# ADCSHubV2.net
KiCad netlist of a schematic drawn in Altium Designer
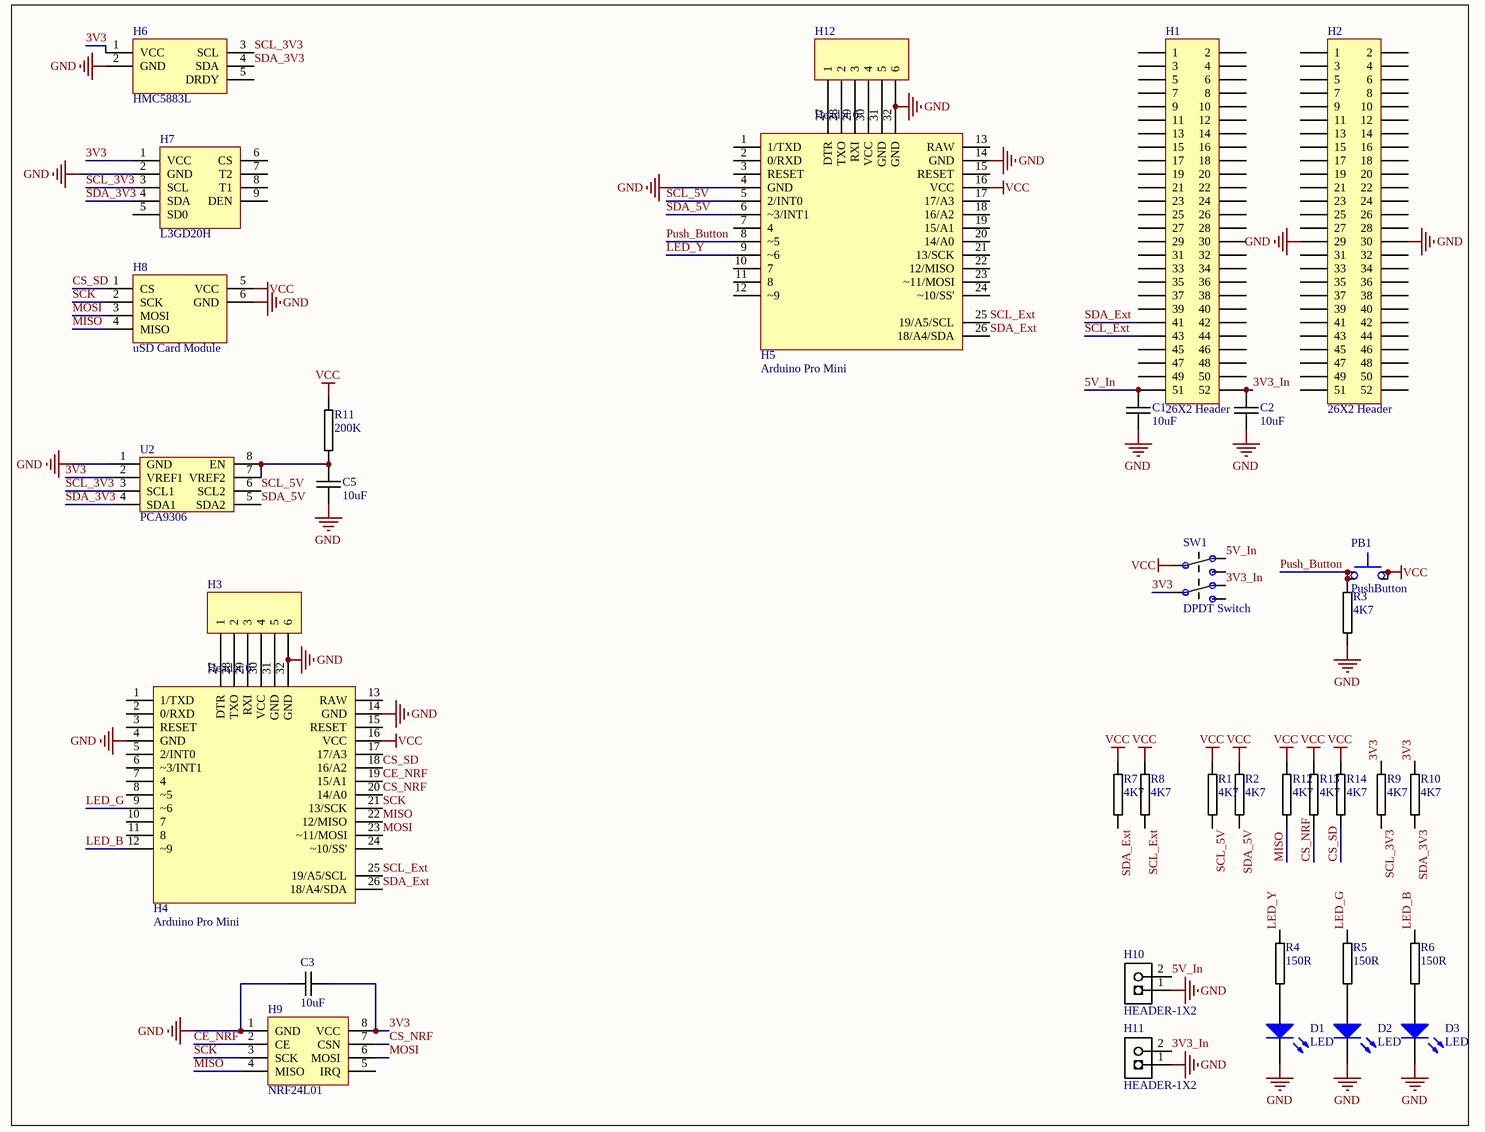
[diagram p0: ADCSHubV2.SchDoc]

(export (version "E")
  (design (tool "Eeschema 10.0.6"))
  (components
    (comp (ref "C1")
      (value "10uF")
      (footprint "0805C-TBD")
      (description "CAPACITOR 0805 CERAMIC")
      (libsource (lib "vh_altium_library") (part "0805C-100nF-25V-X7R-MUR"))
    )
    (comp (ref "C2")
      (value "10uF")
      (footprint "0805C-TBD")
      (description "CAPACITOR 0805 CERAMIC")
      (libsource (lib "vh_altium_library") (part "0805C-100nF-25V-X7R-MUR"))
    )
    (comp (ref "C3")
      (value "10uF")
      (footprint "0805C-GENERIC")
      (description "CAPACITOR 0805 CERAMIC")
      (fields
        (field (name "MANUFACTURER PART NUMBER") "C2012X5R1C106M")
        (field (name "MANUFACTURER") "TDK Corporation")
      )
      (libsource (lib "vh_altium_library") (part "0805C-10UF-16V-X5R-TDK"))
    )
    (comp (ref "C5")
      (value "10uF")
      (footprint "0805C-GENERIC")
      (description "CAPACITOR 0805 CERAMIC")
      (fields
        (field (name "MANUFACTURER PART NUMBER") "C2012X5R1C106M")
        (field (name "MANUFACTURER") "TDK Corporation")
      )
      (libsource (lib "vh_altium_library") (part "0805C-10UF-16V-X5R-TDK"))
    )
    (comp (ref "D1")
      (value "LED")
      (footprint "LED")
      (description "Small LED")
      (libsource (lib "SupportComponents") (part "LED"))
    )
    (comp (ref "D2")
      (value "LED")
      (footprint "LED")
      (description "Small LED")
      (libsource (lib "SupportComponents") (part "LED"))
    )
    (comp (ref "D3")
      (value "LED")
      (footprint "LED")
      (description "Small LED")
      (libsource (lib "SupportComponents") (part "LED"))
    )
    (comp (ref "H1")
      (value "26X2 Header")
      (footprint "26X2 Header")
      (libsource (lib "SupportComponents") (part "26X2 Header"))
    )
    (comp (ref "H2")
      (value "26X2 Header")
      (footprint "26X2 Header")
      (libsource (lib "SupportComponents") (part "26X2 Header"))
    )
    (comp (ref "H3")
      (value "Header 6")
      (footprint "HDR1X6")
      (description "Header, 6-Pin")
      (fields (field (name "PUBLISHER") "Altium Limited"))
      (libsource (lib "Miscellaneous Connectors") (part "Header 6"))
    )
    (comp (ref "H4")
      (value "Arduino Pro Mini")
      (footprint "Arduino Pro Mini")
      (libsource (lib "SupportComponents") (part "Arduino Pro Mini"))
    )
    (comp (ref "H5")
      (value "Arduino Pro Mini")
      (footprint "Arduino Pro Mini")
      (libsource (lib "SupportComponents") (part "Arduino Pro Mini"))
    )
    (comp (ref "H6")
      (value "HMC5883L")
      (footprint "HMC5883L")
      (description "Magnetometer")
      (libsource (lib "SupportComponents") (part "HMC5883L"))
    )
    (comp (ref "H7")
      (value "L3GD20H")
      (footprint "L3GD20H")
      (description "Gyroscope")
      (libsource (lib "SupportComponents") (part "L3GD20H"))
    )
    (comp (ref "H8")
      (value "uSD Card Module")
      (footprint "uSD Card Module")
      (libsource (lib "SupportComponents") (part "uSD Card Module"))
    )
    (comp (ref "H9")
      (value "NRF24L01")
      (footprint "NRF24L01")
      (description "Radio Transceiver")
      (libsource (lib "SupportComponents") (part "NRF24L01"))
    )
    (comp (ref "H10")
      (value "HEADER-1X2")
      (footprint "HEADER-1X2")
      (libsource (lib "vh_altium_library") (part "HEADER-1X2"))
    )
    (comp (ref "H11")
      (value "HEADER-1X2")
      (footprint "HEADER-1X2")
      (libsource (lib "vh_altium_library") (part "HEADER-1X2"))
    )
    (comp (ref "H12")
      (value "Header 6")
      (footprint "HDR1X6")
      (description "Header, 6-Pin")
      (fields (field (name "PUBLISHER") "Altium Limited"))
      (libsource (lib "Miscellaneous Connectors") (part "Header 6"))
    )
    (comp (ref "PB1")
      (value "PushButton")
      (footprint "PushButton")
      (libsource (lib "SupportComponents") (part "PushButton"))
    )
    (comp (ref "R1")
      (value "4K7")
      (footprint "0805R-4K7")
      (description "RESISTOR 0805 1/4 WATT THIN FILM")
      (libsource (lib "vh_altium_library") (part "0805R-4K7"))
    )
    (comp (ref "R2")
      (value "4K7")
      (footprint "0805R-4K7")
      (description "RESISTOR 0805 1/4 WATT THIN FILM")
      (libsource (lib "vh_altium_library") (part "0805R-4K7"))
    )
    (comp (ref "R3")
      (value "4K7")
      (footprint "0805R-4K7")
      (description "RESISTOR 0805 1/4 WATT THIN FILM")
      (libsource (lib "vh_altium_library") (part "0805R-4K7"))
    )
    (comp (ref "R4")
      (value "150R")
      (footprint "0805R-150")
      (description "RESISTOR 0805 1/4 WATT THIN FILM")
      (libsource (lib "vh_altium_library") (part "0805R-150"))
    )
    (comp (ref "R5")
      (value "150R")
      (footprint "0805R-150")
      (description "RESISTOR 0805 1/4 WATT THIN FILM")
      (libsource (lib "vh_altium_library") (part "0805R-150"))
    )
    (comp (ref "R6")
      (value "150R")
      (footprint "0805R-150")
      (description "RESISTOR 0805 1/4 WATT THIN FILM")
      (libsource (lib "vh_altium_library") (part "0805R-150"))
    )
    (comp (ref "R7")
      (value "4K7")
      (footprint "0805R-4K7")
      (description "RESISTOR 0805 1/4 WATT THIN FILM")
      (libsource (lib "vh_altium_library") (part "0805R-4K7"))
    )
    (comp (ref "R8")
      (value "4K7")
      (footprint "0805R-4K7")
      (description "RESISTOR 0805 1/4 WATT THIN FILM")
      (libsource (lib "vh_altium_library") (part "0805R-4K7"))
    )
    (comp (ref "R9")
      (value "4K7")
      (footprint "0805R-4K7")
      (description "RESISTOR 0805 1/4 WATT THIN FILM")
      (libsource (lib "vh_altium_library") (part "0805R-4K7"))
    )
    (comp (ref "R10")
      (value "4K7")
      (footprint "0805R-4K7")
      (description "RESISTOR 0805 1/4 WATT THIN FILM")
      (libsource (lib "vh_altium_library") (part "0805R-4K7"))
    )
    (comp (ref "R11")
      (value "200K")
      (footprint "0805R-4K7")
      (description "RESISTOR 0805 1/4 WATT THIN FILM")
      (libsource (lib "vh_altium_library") (part "0805R-4K7"))
    )
    (comp (ref "R12")
      (value "4K7")
      (footprint "0805R-4K7")
      (description "RESISTOR 0805 1/4 WATT THIN FILM")
      (libsource (lib "vh_altium_library") (part "0805R-4K7"))
    )
    (comp (ref "R13")
      (value "4K7")
      (footprint "0805R-4K7")
      (description "RESISTOR 0805 1/4 WATT THIN FILM")
      (libsource (lib "vh_altium_library") (part "0805R-4K7"))
    )
    (comp (ref "R14")
      (value "4K7")
      (footprint "0805R-4K7")
      (description "RESISTOR 0805 1/4 WATT THIN FILM")
      (libsource (lib "vh_altium_library") (part "0805R-4K7"))
    )
    (comp (ref "SW1")
      (value "DPDT Switch")
      (footprint "DPDT SWITCH")
      (libsource (lib "SupportComponents") (part "DPDT Switch"))
    )
    (comp (ref "U2")
      (value "PCA9306")
      (footprint "PCA9306 (DCT)")
      (description "Dual Bidirectional I2C Voltage Level Translator")
      (libsource (lib "SupportComponents") (part "PCA9306"))
    )
  )
  (nets
    (net (code "1") (name "/3V3") (class "Default")
      (node (ref "C3") (pin "2") (pintype "passive"))
      (node (ref "H6") (pin "1") (pinfunction "VCC_1") (pintype "passive"))
      (node (ref "H7") (pin "1") (pinfunction "VCC_1") (pintype "passive"))
      (node (ref "H9") (pin "8") (pinfunction "VCC_8") (pintype "passive"))
      (node (ref "R10") (pin "1") (pintype "passive"))
      (node (ref "R9") (pin "1") (pintype "passive"))
      (node (ref "SW1") (pin "5") (pinfunction "5_5") (pintype "passive"))
      (node (ref "U2") (pin "2") (pinfunction "VREF1_2") (pintype "passive"))
    )
    (net (code "2") (name "/3V3_In") (class "Default")
      (node (ref "C2") (pin "1") (pintype "passive"))
      (node (ref "H1") (pin "52") (pinfunction "52_52") (pintype "passive"))
      (node (ref "H11") (pin "2") (pintype "passive"))
      (node (ref "SW1") (pin "4") (pinfunction "4_4") (pintype "passive"))
    )
    (net (code "3") (name "/5V_In") (class "Default")
      (node (ref "C1") (pin "1") (pintype "passive"))
      (node (ref "H1") (pin "51") (pinfunction "51_51") (pintype "passive"))
      (node (ref "H10") (pin "2") (pintype "passive"))
      (node (ref "SW1") (pin "1") (pinfunction "1_1") (pintype "passive"))
    )
    (net (code "4") (name "/CE_NRF") (class "Default")
      (node (ref "H4") (pin "19") (pinfunction "15/A1_19") (pintype "passive"))
      (node (ref "H9") (pin "2") (pinfunction "CE_2") (pintype "passive"))
    )
    (net (code "5") (name "/CS_NRF") (class "Default")
      (node (ref "H4") (pin "20") (pinfunction "14/A0_20") (pintype "passive"))
      (node (ref "H9") (pin "7") (pinfunction "CSN_7") (pintype "passive"))
      (node (ref "R13") (pin "2") (pintype "passive"))
    )
    (net (code "6") (name "/CS_SD") (class "Default")
      (node (ref "H4") (pin "18") (pinfunction "16/A2_18") (pintype "passive"))
      (node (ref "H8") (pin "1") (pinfunction "CS_1") (pintype "passive"))
      (node (ref "R14") (pin "2") (pintype "passive"))
    )
    (net (code "7") (name "/LED_B") (class "Default")
      (node (ref "H4") (pin "12") (pinfunction "~9_12") (pintype "passive"))
      (node (ref "R6") (pin "1") (pintype "passive"))
    )
    (net (code "8") (name "/LED_G") (class "Default")
      (node (ref "H4") (pin "9") (pinfunction "~6_9") (pintype "passive"))
      (node (ref "R5") (pin "1") (pintype "passive"))
    )
    (net (code "9") (name "/LED_Y") (class "Default")
      (node (ref "H5") (pin "9") (pinfunction "~6_9") (pintype "passive"))
      (node (ref "R4") (pin "1") (pintype "passive"))
    )
    (net (code "10") (name "/MISO") (class "Default")
      (node (ref "H4") (pin "22") (pinfunction "12/MISO_22") (pintype "passive"))
      (node (ref "H8") (pin "4") (pinfunction "MISO_4") (pintype "passive"))
      (node (ref "H9") (pin "4") (pinfunction "MISO_4") (pintype "passive"))
      (node (ref "R12") (pin "2") (pintype "passive"))
    )
    (net (code "11") (name "/MOSI") (class "Default")
      (node (ref "H4") (pin "23") (pinfunction "~11/MOSI_23") (pintype "passive"))
      (node (ref "H8") (pin "3") (pinfunction "MOSI_3") (pintype "passive"))
      (node (ref "H9") (pin "6") (pinfunction "MOSI_6") (pintype "passive"))
    )
    (net (code "12") (name "/Push_Button") (class "Default")
      (node (ref "H5") (pin "8") (pinfunction "~5_8") (pintype "passive"))
      (node (ref "PB1") (pin "26") (pinfunction "26_26") (pintype "passive"))
      (node (ref "PB1") (pin "28") (pinfunction "28_28") (pintype "passive"))
      (node (ref "R3") (pin "1") (pintype "passive"))
    )
    (net (code "13") (name "/SCK") (class "Default")
      (node (ref "H4") (pin "21") (pinfunction "13/SCK_21") (pintype "passive"))
      (node (ref "H8") (pin "2") (pinfunction "SCK_2") (pintype "passive"))
      (node (ref "H9") (pin "3") (pinfunction "SCK_3") (pintype "passive"))
    )
    (net (code "14") (name "/SCL_3V3") (class "Default")
      (node (ref "H6") (pin "3") (pinfunction "SCL_3") (pintype "passive"))
      (node (ref "H7") (pin "3") (pinfunction "SCL_3") (pintype "passive"))
      (node (ref "R9") (pin "2") (pintype "passive"))
      (node (ref "U2") (pin "3") (pinfunction "SCL1_3") (pintype "passive"))
    )
    (net (code "15") (name "/SCL_5V") (class "Default")
      (node (ref "H5") (pin "5") (pinfunction "2/INT0_5") (pintype "passive"))
      (node (ref "R1") (pin "2") (pintype "passive"))
      (node (ref "U2") (pin "6") (pinfunction "SCL2_6") (pintype "passive"))
    )
    (net (code "16") (name "/SCL_Ext") (class "Default")
      (node (ref "H1") (pin "43") (pinfunction "43_43") (pintype "passive"))
      (node (ref "H4") (pin "25") (pinfunction "19/A5/SCL_25") (pintype "passive"))
      (node (ref "H5") (pin "25") (pinfunction "19/A5/SCL_25") (pintype "passive"))
      (node (ref "R8") (pin "2") (pintype "passive"))
    )
    (net (code "17") (name "/SDA_3V3") (class "Default")
      (node (ref "H6") (pin "4") (pinfunction "SDA_4") (pintype "passive"))
      (node (ref "H7") (pin "4") (pinfunction "SDA_4") (pintype "passive"))
      (node (ref "R10") (pin "2") (pintype "passive"))
      (node (ref "U2") (pin "4") (pinfunction "SDA1_4") (pintype "passive"))
    )
    (net (code "18") (name "/SDA_5V") (class "Default")
      (node (ref "H5") (pin "6") (pinfunction "~3/INT1_6") (pintype "passive"))
      (node (ref "R2") (pin "2") (pintype "passive"))
      (node (ref "U2") (pin "5") (pinfunction "SDA2_5") (pintype "passive"))
    )
    (net (code "19") (name "/SDA_Ext") (class "Default")
      (node (ref "H1") (pin "41") (pinfunction "41_41") (pintype "passive"))
      (node (ref "H4") (pin "26") (pinfunction "18/A4/SDA_26") (pintype "passive"))
      (node (ref "H5") (pin "26") (pinfunction "18/A4/SDA_26") (pintype "passive"))
      (node (ref "R7") (pin "2") (pintype "passive"))
    )
    (net (code "20") (name "GND") (class "Default")
      (node (ref "C1") (pin "2") (pintype "passive"))
      (node (ref "C2") (pin "2") (pintype "passive"))
      (node (ref "C3") (pin "1") (pintype "passive"))
      (node (ref "C5") (pin "2") (pintype "passive"))
      (node (ref "D1") (pin "2") (pinfunction "K_2") (pintype "passive"))
      (node (ref "D2") (pin "2") (pinfunction "K_2") (pintype "passive"))
      (node (ref "D3") (pin "2") (pinfunction "K_2") (pintype "passive"))
      (node (ref "H10") (pin "1") (pintype "passive"))
      (node (ref "H11") (pin "1") (pintype "passive"))
      (node (ref "H12") (pin "6") (pinfunction "6_6") (pintype "passive"))
      (node (ref "H2") (pin "29") (pinfunction "29_29") (pintype "passive"))
      (node (ref "H2") (pin "30") (pinfunction "30_30") (pintype "passive"))
      (node (ref "H3") (pin "6") (pinfunction "6_6") (pintype "passive"))
      (node (ref "H4") (pin "14") (pinfunction "GND_14") (pintype "passive"))
      (node (ref "H4") (pin "32") (pinfunction "GND_32") (pintype "passive"))
      (node (ref "H4") (pin "4") (pinfunction "GND_4") (pintype "passive"))
      (node (ref "H5") (pin "14") (pinfunction "GND_14") (pintype "passive"))
      (node (ref "H5") (pin "32") (pinfunction "GND_32") (pintype "passive"))
      (node (ref "H5") (pin "4") (pinfunction "GND_4") (pintype "passive"))
      (node (ref "H6") (pin "2") (pinfunction "GND_2") (pintype "passive"))
      (node (ref "H7") (pin "2") (pinfunction "GND_2") (pintype "passive"))
      (node (ref "H8") (pin "6") (pinfunction "GND_6") (pintype "passive"))
      (node (ref "H9") (pin "1") (pinfunction "GND_1") (pintype "passive"))
      (node (ref "R3") (pin "2") (pintype "passive"))
      (node (ref "U2") (pin "1") (pinfunction "GND_1") (pintype "passive"))
    )
    (net (code "21") (name "Net-(D1-A)") (class "Default")
      (node (ref "D1") (pin "1") (pinfunction "A_1") (pintype "passive"))
      (node (ref "R4") (pin "2") (pintype "passive"))
    )
    (net (code "22") (name "Net-(D2-A)") (class "Default")
      (node (ref "D2") (pin "1") (pinfunction "A_1") (pintype "passive"))
      (node (ref "R5") (pin "2") (pintype "passive"))
    )
    (net (code "23") (name "Net-(D3-A)") (class "Default")
      (node (ref "D3") (pin "1") (pinfunction "A_1") (pintype "passive"))
      (node (ref "R6") (pin "2") (pintype "passive"))
    )
    (net (code "24") (name "Net-(H3-Pad4)") (class "Default")
      (node (ref "H3") (pin "4") (pinfunction "4_4") (pintype "passive"))
      (node (ref "H4") (pin "30") (pinfunction "VCC_30") (pintype "passive"))
    )
    (net (code "25") (name "Net-(H3-Pad5)") (class "Default")
      (node (ref "H3") (pin "5") (pinfunction "5_5") (pintype "passive"))
      (node (ref "H4") (pin "31") (pinfunction "GND_31") (pintype "passive"))
    )
    (net (code "26") (name "Net-(H4-DTR)") (class "Default")
      (node (ref "H3") (pin "1") (pinfunction "1_1") (pintype "passive"))
      (node (ref "H4") (pin "27") (pinfunction "DTR_27") (pintype "passive"))
    )
    (net (code "27") (name "Net-(H4-RXI)") (class "Default")
      (node (ref "H3") (pin "3") (pinfunction "3_3") (pintype "passive"))
      (node (ref "H4") (pin "29") (pinfunction "RXI_29") (pintype "passive"))
    )
    (net (code "28") (name "Net-(H4-TXO)") (class "Default")
      (node (ref "H3") (pin "2") (pinfunction "2_2") (pintype "passive"))
      (node (ref "H4") (pin "28") (pinfunction "TXO_28") (pintype "passive"))
    )
    (net (code "29") (name "Net-(H5-DTR)") (class "Default")
      (node (ref "H12") (pin "1") (pinfunction "1_1") (pintype "passive"))
      (node (ref "H5") (pin "27") (pinfunction "DTR_27") (pintype "passive"))
    )
    (net (code "30") (name "Net-(H5-RXI)") (class "Default")
      (node (ref "H12") (pin "3") (pinfunction "3_3") (pintype "passive"))
      (node (ref "H5") (pin "29") (pinfunction "RXI_29") (pintype "passive"))
    )
    (net (code "31") (name "Net-(H5-TXO)") (class "Default")
      (node (ref "H12") (pin "2") (pinfunction "2_2") (pintype "passive"))
      (node (ref "H5") (pin "28") (pinfunction "TXO_28") (pintype "passive"))
    )
    (net (code "32") (name "Net-(H12-Pad4)") (class "Default")
      (node (ref "H12") (pin "4") (pinfunction "4_4") (pintype "passive"))
      (node (ref "H5") (pin "30") (pinfunction "VCC_30") (pintype "passive"))
    )
    (net (code "33") (name "Net-(H12-Pad5)") (class "Default")
      (node (ref "H12") (pin "5") (pinfunction "5_5") (pintype "passive"))
      (node (ref "H5") (pin "31") (pinfunction "GND_31") (pintype "passive"))
    )
    (net (code "34") (name "Net-(U2-EN)") (class "Default")
      (node (ref "C5") (pin "1") (pintype "passive"))
      (node (ref "R11") (pin "1") (pintype "passive"))
      (node (ref "U2") (pin "7") (pinfunction "VREF2_7") (pintype "passive"))
      (node (ref "U2") (pin "8") (pinfunction "EN_8") (pintype "passive"))
    )
    (net (code "35") (name "VCC") (class "Default")
      (node (ref "H4") (pin "16") (pinfunction "VCC_16") (pintype "passive"))
      (node (ref "H5") (pin "16") (pinfunction "VCC_16") (pintype "passive"))
      (node (ref "H8") (pin "5") (pinfunction "VCC_5") (pintype "passive"))
      (node (ref "PB1") (pin "27") (pinfunction "27_27") (pintype "passive"))
      (node (ref "PB1") (pin "29") (pinfunction "29_29") (pintype "passive"))
      (node (ref "R1") (pin "1") (pintype "passive"))
      (node (ref "R11") (pin "2") (pintype "passive"))
      (node (ref "R12") (pin "1") (pintype "passive"))
      (node (ref "R13") (pin "1") (pintype "passive"))
      (node (ref "R14") (pin "1") (pintype "passive"))
      (node (ref "R2") (pin "1") (pintype "passive"))
      (node (ref "R7") (pin "1") (pintype "passive"))
      (node (ref "R8") (pin "1") (pintype "passive"))
      (node (ref "SW1") (pin "2") (pinfunction "2_2") (pintype "passive"))
    )
    (net (code "36") (name "unconnected-(H1-Pad1)") (class "Default")
      (node (ref "H1") (pin "1") (pinfunction "1_1") (pintype "passive"))
    )
    (net (code "37") (name "unconnected-(H1-Pad2)") (class "Default")
      (node (ref "H1") (pin "2") (pinfunction "2_2") (pintype "passive"))
    )
    (net (code "38") (name "unconnected-(H1-Pad3)") (class "Default")
      (node (ref "H1") (pin "3") (pinfunction "3_3") (pintype "passive"))
    )
    (net (code "39") (name "unconnected-(H1-Pad4)") (class "Default")
      (node (ref "H1") (pin "4") (pinfunction "4_4") (pintype "passive"))
    )
    (net (code "40") (name "unconnected-(H1-Pad5)") (class "Default")
      (node (ref "H1") (pin "5") (pinfunction "5_5") (pintype "passive"))
    )
    (net (code "41") (name "unconnected-(H1-Pad6)") (class "Default")
      (node (ref "H1") (pin "6") (pinfunction "6_6") (pintype "passive"))
    )
    (net (code "42") (name "unconnected-(H1-Pad7)") (class "Default")
      (node (ref "H1") (pin "7") (pinfunction "7_7") (pintype "passive"))
    )
    (net (code "43") (name "unconnected-(H1-Pad8)") (class "Default")
      (node (ref "H1") (pin "8") (pinfunction "8_8") (pintype "passive"))
    )
    (net (code "44") (name "unconnected-(H1-Pad9)") (class "Default")
      (node (ref "H1") (pin "9") (pinfunction "9_9") (pintype "passive"))
    )
    (net (code "45") (name "unconnected-(H1-Pad10)") (class "Default")
      (node (ref "H1") (pin "10") (pinfunction "10_10") (pintype "passive"))
    )
    (net (code "46") (name "unconnected-(H1-Pad11)") (class "Default")
      (node (ref "H1") (pin "11") (pinfunction "11_11") (pintype "passive"))
    )
    (net (code "47") (name "unconnected-(H1-Pad12)") (class "Default")
      (node (ref "H1") (pin "12") (pinfunction "12_12") (pintype "passive"))
    )
    (net (code "48") (name "unconnected-(H1-Pad13)") (class "Default")
      (node (ref "H1") (pin "13") (pinfunction "13_13") (pintype "passive"))
    )
    (net (code "49") (name "unconnected-(H1-Pad14)") (class "Default")
      (node (ref "H1") (pin "14") (pinfunction "14_14") (pintype "passive"))
    )
    (net (code "50") (name "unconnected-(H1-Pad15)") (class "Default")
      (node (ref "H1") (pin "15") (pinfunction "15_15") (pintype "passive"))
    )
    (net (code "51") (name "unconnected-(H1-Pad16)") (class "Default")
      (node (ref "H1") (pin "16") (pinfunction "16_16") (pintype "passive"))
    )
    (net (code "52") (name "unconnected-(H1-Pad17)") (class "Default")
      (node (ref "H1") (pin "17") (pinfunction "17_17") (pintype "passive"))
    )
    (net (code "53") (name "unconnected-(H1-Pad18)") (class "Default")
      (node (ref "H1") (pin "18") (pinfunction "18_18") (pintype "passive"))
    )
    (net (code "54") (name "unconnected-(H1-Pad19)") (class "Default")
      (node (ref "H1") (pin "19") (pinfunction "19_19") (pintype "passive"))
    )
    (net (code "55") (name "unconnected-(H1-Pad20)") (class "Default")
      (node (ref "H1") (pin "20") (pinfunction "20_20") (pintype "passive"))
    )
    (net (code "56") (name "unconnected-(H1-Pad21)") (class "Default")
      (node (ref "H1") (pin "21") (pinfunction "21_21") (pintype "passive"))
    )
    (net (code "57") (name "unconnected-(H1-Pad22)") (class "Default")
      (node (ref "H1") (pin "22") (pinfunction "22_22") (pintype "passive"))
    )
    (net (code "58") (name "unconnected-(H1-Pad23)") (class "Default")
      (node (ref "H1") (pin "23") (pinfunction "23_23") (pintype "passive"))
    )
    (net (code "59") (name "unconnected-(H1-Pad24)") (class "Default")
      (node (ref "H1") (pin "24") (pinfunction "24_24") (pintype "passive"))
    )
    (net (code "60") (name "unconnected-(H1-Pad25)") (class "Default")
      (node (ref "H1") (pin "25") (pinfunction "25_25") (pintype "passive"))
    )
    (net (code "61") (name "unconnected-(H1-Pad26)") (class "Default")
      (node (ref "H1") (pin "26") (pinfunction "26_26") (pintype "passive"))
    )
    (net (code "62") (name "unconnected-(H1-Pad27)") (class "Default")
      (node (ref "H1") (pin "27") (pinfunction "27_27") (pintype "passive"))
    )
    (net (code "63") (name "unconnected-(H1-Pad28)") (class "Default")
      (node (ref "H1") (pin "28") (pinfunction "28_28") (pintype "passive"))
    )
    (net (code "64") (name "unconnected-(H1-Pad29)") (class "Default")
      (node (ref "H1") (pin "29") (pinfunction "29_29") (pintype "passive"))
    )
    (net (code "65") (name "unconnected-(H1-Pad30)") (class "Default")
      (node (ref "H1") (pin "30") (pinfunction "30_30") (pintype "passive"))
    )
    (net (code "66") (name "unconnected-(H1-Pad31)") (class "Default")
      (node (ref "H1") (pin "31") (pinfunction "31_31") (pintype "passive"))
    )
    (net (code "67") (name "unconnected-(H1-Pad32)") (class "Default")
      (node (ref "H1") (pin "32") (pinfunction "32_32") (pintype "passive"))
    )
    (net (code "68") (name "unconnected-(H1-Pad33)") (class "Default")
      (node (ref "H1") (pin "33") (pinfunction "33_33") (pintype "passive"))
    )
    (net (code "69") (name "unconnected-(H1-Pad34)") (class "Default")
      (node (ref "H1") (pin "34") (pinfunction "34_34") (pintype "passive"))
    )
    (net (code "70") (name "unconnected-(H1-Pad35)") (class "Default")
      (node (ref "H1") (pin "35") (pinfunction "35_35") (pintype "passive"))
    )
    (net (code "71") (name "unconnected-(H1-Pad36)") (class "Default")
      (node (ref "H1") (pin "36") (pinfunction "36_36") (pintype "passive"))
    )
    (net (code "72") (name "unconnected-(H1-Pad37)") (class "Default")
      (node (ref "H1") (pin "37") (pinfunction "37_37") (pintype "passive"))
    )
    (net (code "73") (name "unconnected-(H1-Pad38)") (class "Default")
      (node (ref "H1") (pin "38") (pinfunction "38_38") (pintype "passive"))
    )
    (net (code "74") (name "unconnected-(H1-Pad39)") (class "Default")
      (node (ref "H1") (pin "39") (pinfunction "39_39") (pintype "passive"))
    )
    (net (code "75") (name "unconnected-(H1-Pad40)") (class "Default")
      (node (ref "H1") (pin "40") (pinfunction "40_40") (pintype "passive"))
    )
    (net (code "76") (name "unconnected-(H1-Pad42)") (class "Default")
      (node (ref "H1") (pin "42") (pinfunction "42_42") (pintype "passive"))
    )
    (net (code "77") (name "unconnected-(H1-Pad44)") (class "Default")
      (node (ref "H1") (pin "44") (pinfunction "44_44") (pintype "passive"))
    )
    (net (code "78") (name "unconnected-(H1-Pad45)") (class "Default")
      (node (ref "H1") (pin "45") (pinfunction "45_45") (pintype "passive"))
    )
    (net (code "79") (name "unconnected-(H1-Pad46)") (class "Default")
      (node (ref "H1") (pin "46") (pinfunction "46_46") (pintype "passive"))
    )
    (net (code "80") (name "unconnected-(H1-Pad47)") (class "Default")
      (node (ref "H1") (pin "47") (pinfunction "47_47") (pintype "passive"))
    )
    (net (code "81") (name "unconnected-(H1-Pad48)") (class "Default")
      (node (ref "H1") (pin "48") (pinfunction "48_48") (pintype "passive"))
    )
    (net (code "82") (name "unconnected-(H1-Pad49)") (class "Default")
      (node (ref "H1") (pin "49") (pinfunction "49_49") (pintype "passive"))
    )
    (net (code "83") (name "unconnected-(H1-Pad50)") (class "Default")
      (node (ref "H1") (pin "50") (pinfunction "50_50") (pintype "passive"))
    )
    (net (code "84") (name "unconnected-(H2-Pad1)") (class "Default")
      (node (ref "H2") (pin "1") (pinfunction "1_1") (pintype "passive"))
    )
    (net (code "85") (name "unconnected-(H2-Pad2)") (class "Default")
      (node (ref "H2") (pin "2") (pinfunction "2_2") (pintype "passive"))
    )
    (net (code "86") (name "unconnected-(H2-Pad3)") (class "Default")
      (node (ref "H2") (pin "3") (pinfunction "3_3") (pintype "passive"))
    )
    (net (code "87") (name "unconnected-(H2-Pad4)") (class "Default")
      (node (ref "H2") (pin "4") (pinfunction "4_4") (pintype "passive"))
    )
    (net (code "88") (name "unconnected-(H2-Pad5)") (class "Default")
      (node (ref "H2") (pin "5") (pinfunction "5_5") (pintype "passive"))
    )
    (net (code "89") (name "unconnected-(H2-Pad6)") (class "Default")
      (node (ref "H2") (pin "6") (pinfunction "6_6") (pintype "passive"))
    )
    (net (code "90") (name "unconnected-(H2-Pad7)") (class "Default")
      (node (ref "H2") (pin "7") (pinfunction "7_7") (pintype "passive"))
    )
    (net (code "91") (name "unconnected-(H2-Pad8)") (class "Default")
      (node (ref "H2") (pin "8") (pinfunction "8_8") (pintype "passive"))
    )
    (net (code "92") (name "unconnected-(H2-Pad9)") (class "Default")
      (node (ref "H2") (pin "9") (pinfunction "9_9") (pintype "passive"))
    )
    (net (code "93") (name "unconnected-(H2-Pad10)") (class "Default")
      (node (ref "H2") (pin "10") (pinfunction "10_10") (pintype "passive"))
    )
    (net (code "94") (name "unconnected-(H2-Pad11)") (class "Default")
      (node (ref "H2") (pin "11") (pinfunction "11_11") (pintype "passive"))
    )
    (net (code "95") (name "unconnected-(H2-Pad12)") (class "Default")
      (node (ref "H2") (pin "12") (pinfunction "12_12") (pintype "passive"))
    )
    (net (code "96") (name "unconnected-(H2-Pad13)") (class "Default")
      (node (ref "H2") (pin "13") (pinfunction "13_13") (pintype "passive"))
    )
    (net (code "97") (name "unconnected-(H2-Pad14)") (class "Default")
      (node (ref "H2") (pin "14") (pinfunction "14_14") (pintype "passive"))
    )
    (net (code "98") (name "unconnected-(H2-Pad15)") (class "Default")
      (node (ref "H2") (pin "15") (pinfunction "15_15") (pintype "passive"))
    )
    (net (code "99") (name "unconnected-(H2-Pad16)") (class "Default")
      (node (ref "H2") (pin "16") (pinfunction "16_16") (pintype "passive"))
    )
    (net (code "100") (name "unconnected-(H2-Pad17)") (class "Default")
      (node (ref "H2") (pin "17") (pinfunction "17_17") (pintype "passive"))
    )
    (net (code "101") (name "unconnected-(H2-Pad18)") (class "Default")
      (node (ref "H2") (pin "18") (pinfunction "18_18") (pintype "passive"))
    )
    (net (code "102") (name "unconnected-(H2-Pad19)") (class "Default")
      (node (ref "H2") (pin "19") (pinfunction "19_19") (pintype "passive"))
    )
    (net (code "103") (name "unconnected-(H2-Pad20)") (class "Default")
      (node (ref "H2") (pin "20") (pinfunction "20_20") (pintype "passive"))
    )
    (net (code "104") (name "unconnected-(H2-Pad21)") (class "Default")
      (node (ref "H2") (pin "21") (pinfunction "21_21") (pintype "passive"))
    )
    (net (code "105") (name "unconnected-(H2-Pad22)") (class "Default")
      (node (ref "H2") (pin "22") (pinfunction "22_22") (pintype "passive"))
    )
    (net (code "106") (name "unconnected-(H2-Pad23)") (class "Default")
      (node (ref "H2") (pin "23") (pinfunction "23_23") (pintype "passive"))
    )
    (net (code "107") (name "unconnected-(H2-Pad24)") (class "Default")
      (node (ref "H2") (pin "24") (pinfunction "24_24") (pintype "passive"))
    )
    (net (code "108") (name "unconnected-(H2-Pad25)") (class "Default")
      (node (ref "H2") (pin "25") (pinfunction "25_25") (pintype "passive"))
    )
    (net (code "109") (name "unconnected-(H2-Pad26)") (class "Default")
      (node (ref "H2") (pin "26") (pinfunction "26_26") (pintype "passive"))
    )
    (net (code "110") (name "unconnected-(H2-Pad27)") (class "Default")
      (node (ref "H2") (pin "27") (pinfunction "27_27") (pintype "passive"))
    )
    (net (code "111") (name "unconnected-(H2-Pad28)") (class "Default")
      (node (ref "H2") (pin "28") (pinfunction "28_28") (pintype "passive"))
    )
    (net (code "112") (name "unconnected-(H2-Pad31)") (class "Default")
      (node (ref "H2") (pin "31") (pinfunction "31_31") (pintype "passive"))
    )
    (net (code "113") (name "unconnected-(H2-Pad32)") (class "Default")
      (node (ref "H2") (pin "32") (pinfunction "32_32") (pintype "passive"))
    )
    (net (code "114") (name "unconnected-(H2-Pad33)") (class "Default")
      (node (ref "H2") (pin "33") (pinfunction "33_33") (pintype "passive"))
    )
    (net (code "115") (name "unconnected-(H2-Pad34)") (class "Default")
      (node (ref "H2") (pin "34") (pinfunction "34_34") (pintype "passive"))
    )
    (net (code "116") (name "unconnected-(H2-Pad35)") (class "Default")
      (node (ref "H2") (pin "35") (pinfunction "35_35") (pintype "passive"))
    )
    (net (code "117") (name "unconnected-(H2-Pad36)") (class "Default")
      (node (ref "H2") (pin "36") (pinfunction "36_36") (pintype "passive"))
    )
    (net (code "118") (name "unconnected-(H2-Pad37)") (class "Default")
      (node (ref "H2") (pin "37") (pinfunction "37_37") (pintype "passive"))
    )
    (net (code "119") (name "unconnected-(H2-Pad38)") (class "Default")
      (node (ref "H2") (pin "38") (pinfunction "38_38") (pintype "passive"))
    )
    (net (code "120") (name "unconnected-(H2-Pad39)") (class "Default")
      (node (ref "H2") (pin "39") (pinfunction "39_39") (pintype "passive"))
    )
    (net (code "121") (name "unconnected-(H2-Pad40)") (class "Default")
      (node (ref "H2") (pin "40") (pinfunction "40_40") (pintype "passive"))
    )
    (net (code "122") (name "unconnected-(H2-Pad41)") (class "Default")
      (node (ref "H2") (pin "41") (pinfunction "41_41") (pintype "passive"))
    )
    (net (code "123") (name "unconnected-(H2-Pad42)") (class "Default")
      (node (ref "H2") (pin "42") (pinfunction "42_42") (pintype "passive"))
    )
    (net (code "124") (name "unconnected-(H2-Pad43)") (class "Default")
      (node (ref "H2") (pin "43") (pinfunction "43_43") (pintype "passive"))
    )
    (net (code "125") (name "unconnected-(H2-Pad44)") (class "Default")
      (node (ref "H2") (pin "44") (pinfunction "44_44") (pintype "passive"))
    )
    (net (code "126") (name "unconnected-(H2-Pad45)") (class "Default")
      (node (ref "H2") (pin "45") (pinfunction "45_45") (pintype "passive"))
    )
    (net (code "127") (name "unconnected-(H2-Pad46)") (class "Default")
      (node (ref "H2") (pin "46") (pinfunction "46_46") (pintype "passive"))
    )
    (net (code "128") (name "unconnected-(H2-Pad47)") (class "Default")
      (node (ref "H2") (pin "47") (pinfunction "47_47") (pintype "passive"))
    )
    (net (code "129") (name "unconnected-(H2-Pad48)") (class "Default")
      (node (ref "H2") (pin "48") (pinfunction "48_48") (pintype "passive"))
    )
    (net (code "130") (name "unconnected-(H2-Pad49)") (class "Default")
      (node (ref "H2") (pin "49") (pinfunction "49_49") (pintype "passive"))
    )
    (net (code "131") (name "unconnected-(H2-Pad50)") (class "Default")
      (node (ref "H2") (pin "50") (pinfunction "50_50") (pintype "passive"))
    )
    (net (code "132") (name "unconnected-(H2-Pad51)") (class "Default")
      (node (ref "H2") (pin "51") (pinfunction "51_51") (pintype "passive"))
    )
    (net (code "133") (name "unconnected-(H2-Pad52)") (class "Default")
      (node (ref "H2") (pin "52") (pinfunction "52_52") (pintype "passive"))
    )
    (net (code "134") (name "unconnected-(H4-0{slash}RXD-Pad2)") (class "Default")
      (node (ref "H4") (pin "2") (pinfunction "0/RXD_2") (pintype "passive"))
    )
    (net (code "135") (name "unconnected-(H4-1{slash}TXD-Pad1)") (class "Default")
      (node (ref "H4") (pin "1") (pinfunction "1/TXD_1") (pintype "passive"))
    )
    (net (code "136") (name "unconnected-(H4-2{slash}INT0-Pad5)") (class "Default")
      (node (ref "H4") (pin "5") (pinfunction "2/INT0_5") (pintype "passive"))
    )
    (net (code "137") (name "unconnected-(H4-4-Pad7)") (class "Default")
      (node (ref "H4") (pin "7") (pinfunction "4_7") (pintype "passive"))
    )
    (net (code "138") (name "unconnected-(H4-7-Pad10)") (class "Default")
      (node (ref "H4") (pin "10") (pinfunction "7_10") (pintype "passive"))
    )
    (net (code "139") (name "unconnected-(H4-8-Pad11)") (class "Default")
      (node (ref "H4") (pin "11") (pinfunction "8_11") (pintype "passive"))
    )
    (net (code "140") (name "unconnected-(H4-17{slash}A3-Pad17)") (class "Default")
      (node (ref "H4") (pin "17") (pinfunction "17/A3_17") (pintype "passive"))
    )
    (net (code "141") (name "unconnected-(H4-RAW-Pad13)") (class "Default")
      (node (ref "H4") (pin "13") (pinfunction "RAW_13") (pintype "passive"))
    )
    (net (code "142") (name "unconnected-(H4-RESET-Pad3)") (class "Default")
      (node (ref "H4") (pin "3") (pinfunction "RESET_3") (pintype "passive"))
    )
    (net (code "143") (name "unconnected-(H4-RESET-Pad15)") (class "Default")
      (node (ref "H4") (pin "15") (pinfunction "RESET_15") (pintype "passive"))
    )
    (net (code "144") (name "unconnected-(H4-~3{slash}INT1-Pad6)") (class "Default")
      (node (ref "H4") (pin "6") (pinfunction "~3/INT1_6") (pintype "passive"))
    )
    (net (code "145") (name "unconnected-(H4-~5-Pad8)") (class "Default")
      (node (ref "H4") (pin "8") (pinfunction "~5_8") (pintype "passive"))
    )
    (net (code "146") (name "unconnected-(H4-~10{slash}SS'-Pad24)") (class "Default")
      (node (ref "H4") (pin "24") (pinfunction "~10/SS'_24") (pintype "passive"))
    )
    (net (code "147") (name "unconnected-(H5-0{slash}RXD-Pad2)") (class "Default")
      (node (ref "H5") (pin "2") (pinfunction "0/RXD_2") (pintype "passive"))
    )
    (net (code "148") (name "unconnected-(H5-1{slash}TXD-Pad1)") (class "Default")
      (node (ref "H5") (pin "1") (pinfunction "1/TXD_1") (pintype "passive"))
    )
    (net (code "149") (name "unconnected-(H5-4-Pad7)") (class "Default")
      (node (ref "H5") (pin "7") (pinfunction "4_7") (pintype "passive"))
    )
    (net (code "150") (name "unconnected-(H5-7-Pad10)") (class "Default")
      (node (ref "H5") (pin "10") (pinfunction "7_10") (pintype "passive"))
    )
    (net (code "151") (name "unconnected-(H5-8-Pad11)") (class "Default")
      (node (ref "H5") (pin "11") (pinfunction "8_11") (pintype "passive"))
    )
    (net (code "152") (name "unconnected-(H5-12{slash}MISO-Pad22)") (class "Default")
      (node (ref "H5") (pin "22") (pinfunction "12/MISO_22") (pintype "passive"))
    )
    (net (code "153") (name "unconnected-(H5-13{slash}SCK-Pad21)") (class "Default")
      (node (ref "H5") (pin "21") (pinfunction "13/SCK_21") (pintype "passive"))
    )
    (net (code "154") (name "unconnected-(H5-14{slash}A0-Pad20)") (class "Default")
      (node (ref "H5") (pin "20") (pinfunction "14/A0_20") (pintype "passive"))
    )
    (net (code "155") (name "unconnected-(H5-15{slash}A1-Pad19)") (class "Default")
      (node (ref "H5") (pin "19") (pinfunction "15/A1_19") (pintype "passive"))
    )
    (net (code "156") (name "unconnected-(H5-16{slash}A2-Pad18)") (class "Default")
      (node (ref "H5") (pin "18") (pinfunction "16/A2_18") (pintype "passive"))
    )
    (net (code "157") (name "unconnected-(H5-17{slash}A3-Pad17)") (class "Default")
      (node (ref "H5") (pin "17") (pinfunction "17/A3_17") (pintype "passive"))
    )
    (net (code "158") (name "unconnected-(H5-RAW-Pad13)") (class "Default")
      (node (ref "H5") (pin "13") (pinfunction "RAW_13") (pintype "passive"))
    )
    (net (code "159") (name "unconnected-(H5-RESET-Pad3)") (class "Default")
      (node (ref "H5") (pin "3") (pinfunction "RESET_3") (pintype "passive"))
    )
    (net (code "160") (name "unconnected-(H5-RESET-Pad15)") (class "Default")
      (node (ref "H5") (pin "15") (pinfunction "RESET_15") (pintype "passive"))
    )
    (net (code "161") (name "unconnected-(H5-~9-Pad12)") (class "Default")
      (node (ref "H5") (pin "12") (pinfunction "~9_12") (pintype "passive"))
    )
    (net (code "162") (name "unconnected-(H5-~10{slash}SS'-Pad24)") (class "Default")
      (node (ref "H5") (pin "24") (pinfunction "~10/SS'_24") (pintype "passive"))
    )
    (net (code "163") (name "unconnected-(H5-~11{slash}MOSI-Pad23)") (class "Default")
      (node (ref "H5") (pin "23") (pinfunction "~11/MOSI_23") (pintype "passive"))
    )
    (net (code "164") (name "unconnected-(H6-DRDY-Pad5)") (class "Default")
      (node (ref "H6") (pin "5") (pinfunction "DRDY_5") (pintype "passive"))
    )
    (net (code "165") (name "unconnected-(H7-CS-Pad6)") (class "Default")
      (node (ref "H7") (pin "6") (pinfunction "CS_6") (pintype "passive"))
    )
    (net (code "166") (name "unconnected-(H7-DEN-Pad9)") (class "Default")
      (node (ref "H7") (pin "9") (pinfunction "DEN_9") (pintype "passive"))
    )
    (net (code "167") (name "unconnected-(H7-SD0-Pad5)") (class "Default")
      (node (ref "H7") (pin "5") (pinfunction "SD0_5") (pintype "passive"))
    )
    (net (code "168") (name "unconnected-(H7-T1-Pad8)") (class "Default")
      (node (ref "H7") (pin "8") (pinfunction "T1_8") (pintype "passive"))
    )
    (net (code "169") (name "unconnected-(H7-T2-Pad7)") (class "Default")
      (node (ref "H7") (pin "7") (pinfunction "T2_7") (pintype "passive"))
    )
    (net (code "170") (name "unconnected-(H9-IRQ-Pad5)") (class "Default")
      (node (ref "H9") (pin "5") (pinfunction "IRQ_5") (pintype "passive"))
    )
    (net (code "171") (name "unconnected-(SW1-Pad3)") (class "Default")
      (node (ref "SW1") (pin "3") (pinfunction "3_3") (pintype "passive"))
    )
    (net (code "172") (name "unconnected-(SW1-Pad6)") (class "Default")
      (node (ref "SW1") (pin "6") (pinfunction "6_6") (pintype "passive"))
    )
  )
)
